# drveth.net
KiCad netlist of a schematic drawn in Altium Designer
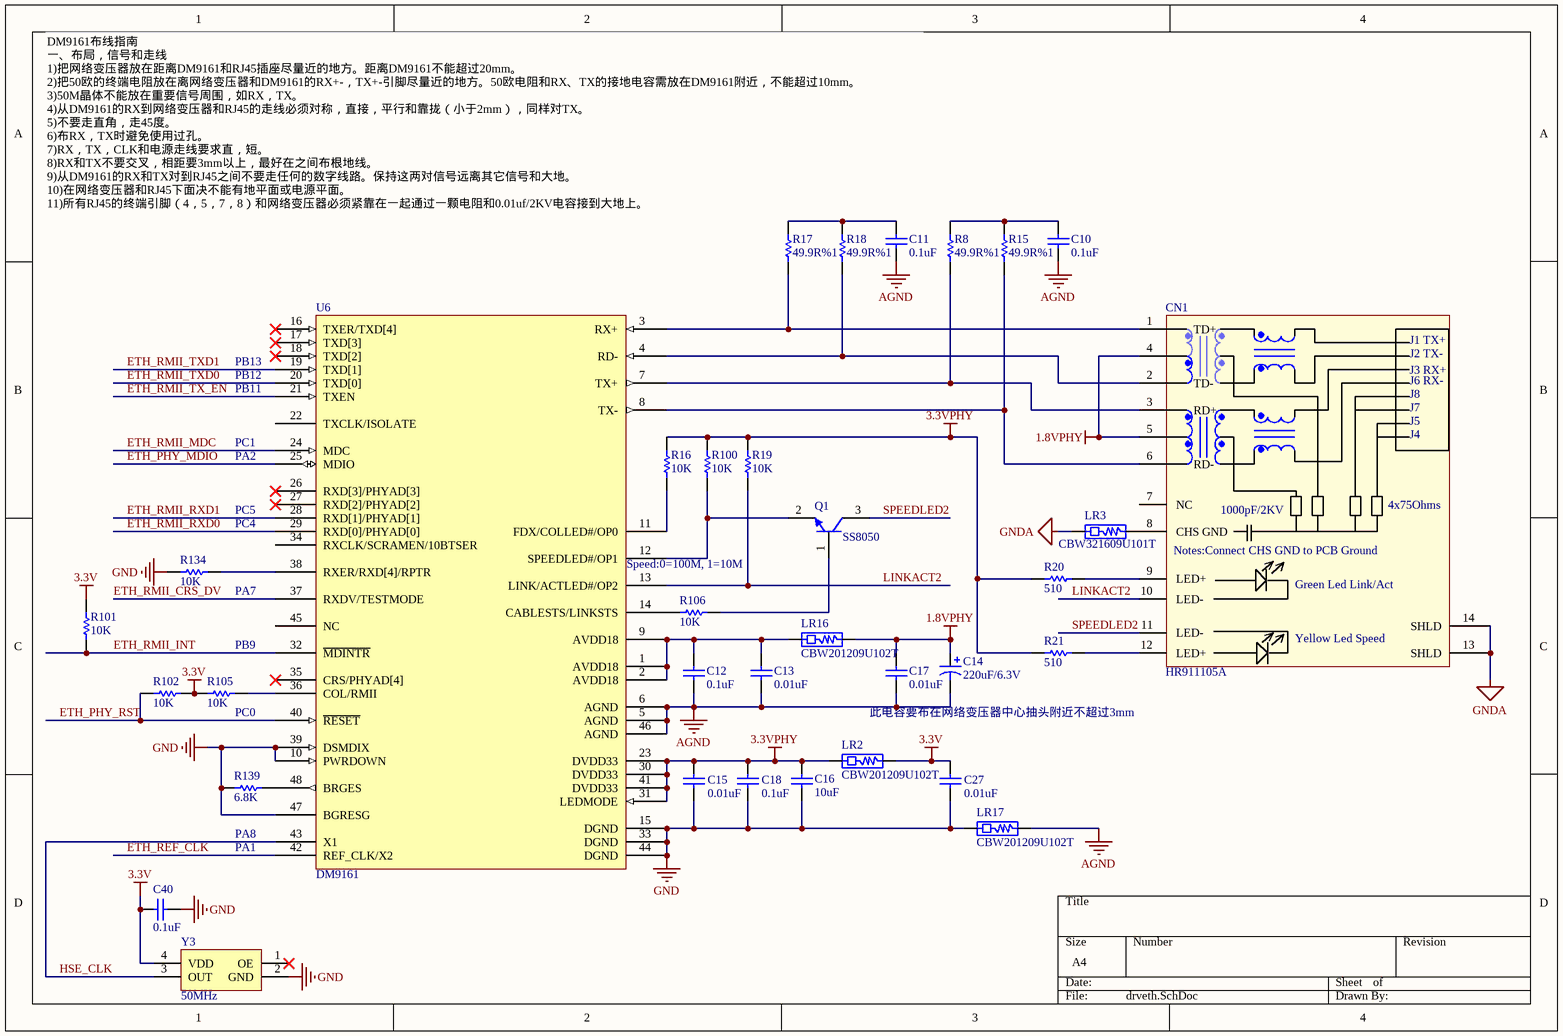
[diagram p0: drveth.SchDoc]

(export (version "E")
  (design (tool "Eeschema 10.0.6"))
  (components
    (comp (ref "C10")
      (value "0.1uF")
      (footprint "CAPC2012M")
      (description "Capacitor")
      (fields (field (name "PUBLISHER") "Altium Limited"))
      (libsource (lib "Miscellaneous Devices") (part "Cap"))
    )
    (comp (ref "C11")
      (value "0.1uF")
      (footprint "CAPC2012M")
      (description "Capacitor")
      (fields (field (name "PUBLISHER") "Altium Limited"))
      (libsource (lib "Miscellaneous Devices") (part "Cap"))
    )
    (comp (ref "C12")
      (value "0.1uF")
      (footprint "CAPC2012M")
      (description "Capacitor")
      (fields (field (name "PUBLISHER") "Altium Limited"))
      (libsource (lib "Miscellaneous Devices") (part "Cap"))
    )
    (comp (ref "C13")
      (value "0.01uF")
      (footprint "CAPC2012M")
      (description "Capacitor")
      (fields (field (name "PUBLISHER") "Altium Limited"))
      (libsource (lib "Miscellaneous Devices") (part "Cap"))
    )
    (comp (ref "C14")
      (value "220uF/6.3V")
      (footprint "CAPC3528MS")
      (description "Polarized Capacitor (Radial)")
      (fields (field (name "PUBLISHER") "Altium Limited"))
      (libsource (lib "Miscellaneous Devices") (part "Cap Pol1"))
    )
    (comp (ref "C15")
      (value "0.01uF")
      (footprint "CAPC2012M")
      (description "Capacitor")
      (fields (field (name "PUBLISHER") "Altium Limited"))
      (libsource (lib "Miscellaneous Devices") (part "Cap"))
    )
    (comp (ref "C16")
      (value "10uF")
      (footprint "CAPC2012M")
      (description "Capacitor")
      (fields (field (name "PUBLISHER") "Altium Limited"))
      (libsource (lib "Miscellaneous Devices") (part "Cap"))
    )
    (comp (ref "C17")
      (value "0.01uF")
      (footprint "CAPC2012M")
      (description "Capacitor")
      (fields (field (name "PUBLISHER") "Altium Limited"))
      (libsource (lib "Miscellaneous Devices") (part "Cap"))
    )
    (comp (ref "C18")
      (value "0.1uF")
      (footprint "CAPC2012M")
      (description "Capacitor")
      (fields (field (name "PUBLISHER") "Altium Limited"))
      (libsource (lib "Miscellaneous Devices") (part "Cap"))
    )
    (comp (ref "C27")
      (value "0.01uF")
      (footprint "CAPC2012M")
      (description "Capacitor")
      (fields (field (name "PUBLISHER") "Altium Limited"))
      (libsource (lib "Miscellaneous Devices") (part "Cap"))
    )
    (comp (ref "C40")
      (value "0.1uF")
      (footprint "CAPC2012M")
      (description "Capacitor")
      (fields (field (name "PUBLISHER") "Altium Limited"))
      (libsource (lib "Miscellaneous Devices") (part "Cap"))
    )
    (comp (ref "CN1")
      (value "HR911105A")
      (footprint "HR911105A(RJ-45)")
      (libsource (lib "UserSchDev") (part "HR911105A"))
    )
    (comp (ref "LR2")
      (value "CBW201209U102T")
      (footprint "INDC2012M")
      (description "EMI FILTERS,DC Resistance max.0.05~1.5 ohms,10 ~ 1000 ohms at 100MHz  Frequency")
      (libsource (lib "UserLib") (part "BLM10/11/21/31/41"))
    )
    (comp (ref "LR3")
      (value "CBW321609U101T")
      (footprint "INDC3216M")
      (description "EMI FILTERS,DC Resistance max.0.05~1.5 ohms,10 ~ 1000 ohms at 100MHz  Frequency")
      (libsource (lib "UserLib") (part "BLM10/11/21/31/41"))
    )
    (comp (ref "LR16")
      (value "CBW201209U102T")
      (footprint "INDC2012M")
      (description "EMI FILTERS,DC Resistance max.0.05~1.5 ohms,10 ~ 1000 ohms at 100MHz  Frequency")
      (libsource (lib "UserLib") (part "BLM10/11/21/31/41"))
    )
    (comp (ref "LR17")
      (value "CBW201209U102T")
      (footprint "INDC2012M")
      (description "EMI FILTERS,DC Resistance max.0.05~1.5 ohms,10 ~ 1000 ohms at 100MHz  Frequency")
      (libsource (lib "UserLib") (part "BLM10/11/21/31/41"))
    )
    (comp (ref "Q1")
      (value "SS8050")
      (footprint "SOT-23_N")
      (description "NPN BISS Transistor")
      (fields (field (name "PUBLISHER") "Altium Limited"))
      (libsource (lib "Philips Discrete BJT - Low Power") (part "PMMT491A"))
    )
    (comp (ref "R8")
      (value "49.9R%1")
      (footprint "RESC2012M")
      (description "Resistor")
      (fields (field (name "PUBLISHER") "Altium Limited"))
      (libsource (lib "Miscellaneous Devices") (part "Res1"))
    )
    (comp (ref "R15")
      (value "49.9R%1")
      (footprint "RESC2012M")
      (description "Resistor")
      (fields (field (name "PUBLISHER") "Altium Limited"))
      (libsource (lib "Miscellaneous Devices") (part "Res1"))
    )
    (comp (ref "R16")
      (value "10K")
      (footprint "RESC2012M")
      (description "Resistor")
      (fields (field (name "PUBLISHER") "Altium Limited"))
      (libsource (lib "Miscellaneous Devices") (part "Res1"))
    )
    (comp (ref "R17")
      (value "49.9R%1")
      (footprint "RESC2012M")
      (description "Resistor")
      (fields (field (name "PUBLISHER") "Altium Limited"))
      (libsource (lib "Miscellaneous Devices") (part "Res1"))
    )
    (comp (ref "R18")
      (value "49.9R%1")
      (footprint "RESC2012M")
      (description "Resistor")
      (fields (field (name "PUBLISHER") "Altium Limited"))
      (libsource (lib "Miscellaneous Devices") (part "Res1"))
    )
    (comp (ref "R19")
      (value "10K")
      (footprint "RESC2012M")
      (description "Resistor")
      (fields (field (name "PUBLISHER") "Altium Limited"))
      (libsource (lib "Miscellaneous Devices") (part "Res1"))
    )
    (comp (ref "R20")
      (value "510")
      (footprint "RESC2012M")
      (description "Resistor")
      (fields (field (name "PUBLISHER") "Altium Limited"))
      (libsource (lib "Miscellaneous Devices") (part "Res1"))
    )
    (comp (ref "R21")
      (value "510")
      (footprint "RESC2012M")
      (description "Resistor")
      (fields (field (name "PUBLISHER") "Altium Limited"))
      (libsource (lib "Miscellaneous Devices") (part "Res1"))
    )
    (comp (ref "R100")
      (value "10K")
      (footprint "RESC2012M")
      (description "Resistor")
      (fields (field (name "PUBLISHER") "Altium Limited"))
      (libsource (lib "Miscellaneous Devices") (part "Res1"))
    )
    (comp (ref "R101")
      (value "10K")
      (footprint "RESC2012M")
      (description "Resistor")
      (fields (field (name "PUBLISHER") "Altium Limited"))
      (libsource (lib "Miscellaneous Devices") (part "Res1"))
    )
    (comp (ref "R102")
      (value "10K")
      (footprint "RESC2012M")
      (description "Resistor")
      (fields (field (name "PUBLISHER") "Altium Limited"))
      (libsource (lib "Miscellaneous Devices") (part "Res1"))
    )
    (comp (ref "R105")
      (value "10K")
      (footprint "RESC2012M")
      (description "Resistor")
      (fields (field (name "PUBLISHER") "Altium Limited"))
      (libsource (lib "Miscellaneous Devices") (part "Res1"))
    )
    (comp (ref "R106")
      (value "10K")
      (footprint "RESC2012M")
      (description "Resistor")
      (fields (field (name "PUBLISHER") "Altium Limited"))
      (libsource (lib "Miscellaneous Devices") (part "Res1"))
    )
    (comp (ref "R134")
      (value "10K")
      (footprint "RESC2012M")
      (description "Resistor")
      (fields (field (name "PUBLISHER") "Altium Limited"))
      (libsource (lib "Miscellaneous Devices") (part "Res1"))
    )
    (comp (ref "R139")
      (value "6.8K")
      (footprint "RESC2012M")
      (description "Resistor")
      (fields (field (name "PUBLISHER") "Altium Limited"))
      (libsource (lib "Miscellaneous Devices") (part "Res1"))
    )
    (comp (ref "U6")
      (value "DM9161")
      (footprint "LQFP48_L")
      (description "网络芯片")
      (libsource (lib "UserSchDev") (part "DM9161"))
    )
    (comp (ref "Y3")
      (value "50MHz")
      (footprint "X-CP3225")
      (description "贴片有源晶振")
      (fields (field (name "Comment") "XATLS"))
      (libsource (lib "UserSchDev") (part "XATLS"))
    )
  )
  (nets
    (net (code "1") (name "/ETH_PHY_MDIO") (class "Default")
      (node (ref "U6") (pin "25") (pinfunction "MDIO_25") (pintype "bidirectional"))
    )
    (net (code "2") (name "/ETH_PHY_RST") (class "Default")
      (node (ref "R102") (pin "1") (pinfunction "1_1") (pintype "passive"))
      (node (ref "U6") (pin "40") (pinfunction "~{RESET}_40") (pintype "input"))
    )
    (net (code "3") (name "/ETH_REF_CLK") (class "Default")
      (node (ref "U6") (pin "42") (pinfunction "REF_CLK/X2_42") (pintype "passive"))
    )
    (net (code "4") (name "/ETH_RMII_CRS_DV") (class "Default")
      (node (ref "U6") (pin "37") (pinfunction "RXDV/TESTMODE_37") (pintype "passive"))
    )
    (net (code "5") (name "/ETH_RMII_INT") (class "Default")
      (node (ref "R101") (pin "2") (pinfunction "2_2") (pintype "passive"))
      (node (ref "U6") (pin "32") (pinfunction "~{MDINTR}_32") (pintype "passive"))
    )
    (net (code "6") (name "/ETH_RMII_MDC") (class "Default")
      (node (ref "U6") (pin "24") (pinfunction "MDC_24") (pintype "input"))
    )
    (net (code "7") (name "/ETH_RMII_RXD0") (class "Default")
      (node (ref "U6") (pin "29") (pinfunction "RXD[0]/PHYAD[0]_29") (pintype "passive"))
    )
    (net (code "8") (name "/ETH_RMII_RXD1") (class "Default")
      (node (ref "U6") (pin "28") (pinfunction "RXD[1]/PHYAD[1]_28") (pintype "passive"))
    )
    (net (code "9") (name "/ETH_RMII_TXD0") (class "Default")
      (node (ref "U6") (pin "20") (pinfunction "TXD[0]_20") (pintype "input"))
    )
    (net (code "10") (name "/ETH_RMII_TXD1") (class "Default")
      (node (ref "U6") (pin "19") (pinfunction "TXD[1]_19") (pintype "input"))
    )
    (net (code "11") (name "/ETH_RMII_TX_EN") (class "Default")
      (node (ref "U6") (pin "21") (pinfunction "TXEN_21") (pintype "input"))
    )
    (net (code "12") (name "/HSE_CLK") (class "Default")
      (node (ref "U6") (pin "43") (pinfunction "X1_43") (pintype "passive"))
      (node (ref "Y3") (pin "3") (pinfunction "OUT_3") (pintype "passive"))
    )
    (net (code "13") (name "/LINKACT2") (class "Default")
      (node (ref "CN1") (pin "10") (pinfunction "LED-_10") (pintype "passive"))
      (node (ref "R19") (pin "2") (pinfunction "2_2") (pintype "passive"))
      (node (ref "U6") (pin "13") (pinfunction "LINK/ACTLED#/OP2_13") (pintype "passive"))
    )
    (net (code "14") (name "/SPEEDLED2") (class "Default")
      (node (ref "CN1") (pin "11") (pinfunction "LED-_11") (pintype "passive"))
      (node (ref "Q1") (pin "3") (pinfunction "C_3") (pintype "passive"))
    )
    (net (code "15") (name "1.8VPHY") (class "Default")
      (node (ref "C14") (pin "1") (pinfunction "1_1") (pintype "passive"))
      (node (ref "C17") (pin "1") (pinfunction "1_1") (pintype "passive"))
      (node (ref "CN1") (pin "4") (pintype "passive"))
      (node (ref "CN1") (pin "5") (pintype "passive"))
      (node (ref "LR16") (pin "1") (pinfunction "1_1") (pintype "passive"))
    )
    (net (code "16") (name "3.3V") (class "Default")
      (node (ref "C27") (pin "1") (pinfunction "1_1") (pintype "passive"))
      (node (ref "C40") (pin "1") (pinfunction "1_1") (pintype "passive"))
      (node (ref "LR2") (pin "1") (pinfunction "1_1") (pintype "passive"))
      (node (ref "R101") (pin "1") (pinfunction "1_1") (pintype "passive"))
      (node (ref "R102") (pin "2") (pinfunction "2_2") (pintype "passive"))
      (node (ref "R105") (pin "1") (pinfunction "1_1") (pintype "passive"))
      (node (ref "Y3") (pin "4") (pinfunction "VDD_4") (pintype "passive"))
    )
    (net (code "17") (name "3.3VPHY") (class "Default")
      (node (ref "C15") (pin "1") (pinfunction "1_1") (pintype "passive"))
      (node (ref "C16") (pin "1") (pinfunction "1_1") (pintype "passive"))
      (node (ref "C18") (pin "1") (pinfunction "1_1") (pintype "passive"))
      (node (ref "LR2") (pin "2") (pinfunction "2_2") (pintype "passive"))
      (node (ref "R100") (pin "1") (pinfunction "1_1") (pintype "passive"))
      (node (ref "R16") (pin "1") (pinfunction "1_1") (pintype "passive"))
      (node (ref "R19") (pin "1") (pinfunction "1_1") (pintype "passive"))
      (node (ref "R20") (pin "1") (pinfunction "1_1") (pintype "passive"))
      (node (ref "R21") (pin "1") (pinfunction "1_1") (pintype "passive"))
      (node (ref "U6") (pin "23") (pinfunction "DVDD33_23") (pintype "power_in"))
      (node (ref "U6") (pin "30") (pinfunction "DVDD33_30") (pintype "power_in"))
      (node (ref "U6") (pin "31") (pinfunction "LEDMODE_31") (pintype "input"))
      (node (ref "U6") (pin "41") (pinfunction "DVDD33_41") (pintype "power_in"))
    )
    (net (code "18") (name "AGND") (class "Default")
      (node (ref "C10") (pin "2") (pinfunction "2_2") (pintype "passive"))
      (node (ref "C11") (pin "2") (pinfunction "2_2") (pintype "passive"))
      (node (ref "C12") (pin "2") (pinfunction "2_2") (pintype "passive"))
      (node (ref "C13") (pin "2") (pinfunction "2_2") (pintype "passive"))
      (node (ref "C14") (pin "2") (pinfunction "2_2") (pintype "passive"))
      (node (ref "C17") (pin "2") (pinfunction "2_2") (pintype "passive"))
      (node (ref "LR17") (pin "1") (pinfunction "1_1") (pintype "passive"))
      (node (ref "U6") (pin "46") (pinfunction "AGND_46") (pintype "power_in"))
      (node (ref "U6") (pin "5") (pinfunction "AGND_5") (pintype "power_in"))
      (node (ref "U6") (pin "6") (pinfunction "AGND_6") (pintype "power_in"))
    )
    (net (code "19") (name "GND") (class "Default")
      (node (ref "C15") (pin "2") (pinfunction "2_2") (pintype "passive"))
      (node (ref "C16") (pin "2") (pinfunction "2_2") (pintype "passive"))
      (node (ref "C18") (pin "2") (pinfunction "2_2") (pintype "passive"))
      (node (ref "C27") (pin "2") (pinfunction "2_2") (pintype "passive"))
      (node (ref "C40") (pin "2") (pinfunction "2_2") (pintype "passive"))
      (node (ref "LR17") (pin "2") (pinfunction "2_2") (pintype "passive"))
      (node (ref "R134") (pin "1") (pinfunction "1_1") (pintype "passive"))
      (node (ref "R139") (pin "1") (pinfunction "1_1") (pintype "passive"))
      (node (ref "U6") (pin "10") (pinfunction "PWRDOWN_10") (pintype "input"))
      (node (ref "U6") (pin "15") (pinfunction "DGND_15") (pintype "power_in"))
      (node (ref "U6") (pin "33") (pinfunction "DGND_33") (pintype "passive"))
      (node (ref "U6") (pin "39") (pinfunction "DSMDIX_39") (pintype "input"))
      (node (ref "U6") (pin "44") (pinfunction "DGND_44") (pintype "passive"))
      (node (ref "U6") (pin "47") (pinfunction "BGRESG_47") (pintype "power_in"))
      (node (ref "Y3") (pin "2") (pinfunction "GND_2") (pintype "passive"))
    )
    (net (code "20") (name "GNDA") (class "Default")
      (node (ref "CN1") (pin "13") (pinfunction "SHLD_13") (pintype "passive"))
      (node (ref "CN1") (pin "14") (pinfunction "SHLD_14") (pintype "passive"))
      (node (ref "LR3") (pin "2") (pinfunction "2_2") (pintype "passive"))
    )
    (net (code "21") (name "Net-(C10-Pad1)") (class "Default")
      (node (ref "C10") (pin "1") (pinfunction "1_1") (pintype "passive"))
      (node (ref "R15") (pin "1") (pinfunction "1_1") (pintype "passive"))
      (node (ref "R8") (pin "1") (pinfunction "1_1") (pintype "passive"))
    )
    (net (code "22") (name "Net-(C11-Pad1)") (class "Default")
      (node (ref "C11") (pin "1") (pinfunction "1_1") (pintype "passive"))
      (node (ref "R17") (pin "1") (pinfunction "1_1") (pintype "passive"))
      (node (ref "R18") (pin "1") (pinfunction "1_1") (pintype "passive"))
    )
    (net (code "23") (name "Net-(C12-Pad1)") (class "Default")
      (node (ref "C12") (pin "1") (pinfunction "1_1") (pintype "passive"))
      (node (ref "C13") (pin "1") (pinfunction "1_1") (pintype "passive"))
      (node (ref "LR16") (pin "2") (pinfunction "2_2") (pintype "passive"))
      (node (ref "U6") (pin "1") (pinfunction "AVDD18_1") (pintype "power_in"))
      (node (ref "U6") (pin "2") (pinfunction "AVDD18_2") (pintype "power_in"))
      (node (ref "U6") (pin "9") (pinfunction "AVDD18_9") (pintype "power_in"))
    )
    (net (code "24") (name "Net-(CN1-CHS_GND)") (class "Default")
      (node (ref "CN1") (pin "8") (pinfunction "CHS_GND_8") (pintype "passive"))
      (node (ref "LR3") (pin "1") (pinfunction "1_1") (pintype "passive"))
    )
    (net (code "25") (name "Net-(CN1-LED+-Pad9)") (class "Default")
      (node (ref "CN1") (pin "9") (pinfunction "LED+_9") (pintype "passive"))
      (node (ref "R20") (pin "2") (pinfunction "2_2") (pintype "passive"))
    )
    (net (code "26") (name "Net-(CN1-LED+-Pad12)") (class "Default")
      (node (ref "CN1") (pin "12") (pinfunction "LED+_12") (pintype "passive"))
      (node (ref "R21") (pin "2") (pinfunction "2_2") (pintype "passive"))
    )
    (net (code "27") (name "Net-(CN1-RD+)") (class "Default")
      (node (ref "CN1") (pin "3") (pinfunction "RD+_3") (pintype "passive"))
      (node (ref "R8") (pin "2") (pinfunction "2_2") (pintype "passive"))
      (node (ref "U6") (pin "7") (pinfunction "TX+_7") (pintype "output"))
    )
    (net (code "28") (name "Net-(CN1-RD-)") (class "Default")
      (node (ref "CN1") (pin "6") (pinfunction "RD-_6") (pintype "passive"))
      (node (ref "R15") (pin "2") (pinfunction "2_2") (pintype "passive"))
      (node (ref "U6") (pin "8") (pinfunction "TX-_8") (pintype "output"))
    )
    (net (code "29") (name "Net-(CN1-TD+)") (class "Default")
      (node (ref "CN1") (pin "1") (pinfunction "TD+_1") (pintype "passive"))
      (node (ref "R17") (pin "2") (pinfunction "2_2") (pintype "passive"))
      (node (ref "U6") (pin "3") (pinfunction "RX+_3") (pintype "input"))
    )
    (net (code "30") (name "Net-(CN1-TD-)") (class "Default")
      (node (ref "CN1") (pin "2") (pinfunction "TD-_2") (pintype "passive"))
      (node (ref "R18") (pin "2") (pinfunction "2_2") (pintype "passive"))
      (node (ref "U6") (pin "4") (pinfunction "RD-_4") (pintype "input"))
    )
    (net (code "31") (name "Net-(Q1-B)") (class "Default")
      (node (ref "Q1") (pin "1") (pinfunction "B_1") (pintype "passive"))
      (node (ref "R106") (pin "2") (pinfunction "2_2") (pintype "passive"))
    )
    (net (code "32") (name "Net-(Q1-E)") (class "Default")
      (node (ref "Q1") (pin "2") (pinfunction "E_2") (pintype "passive"))
      (node (ref "R100") (pin "2") (pinfunction "2_2") (pintype "passive"))
      (node (ref "U6") (pin "12") (pinfunction "SPEEDLED#/OP1_12") (pintype "passive"))
    )
    (net (code "33") (name "Net-(U6-BRGES)") (class "Default")
      (node (ref "R139") (pin "2") (pinfunction "2_2") (pintype "passive"))
      (node (ref "U6") (pin "48") (pinfunction "BRGES_48") (pintype "output"))
    )
    (net (code "34") (name "Net-(U6-CABLESTS{slash}LINKSTS)") (class "Default")
      (node (ref "R106") (pin "1") (pinfunction "1_1") (pintype "passive"))
      (node (ref "U6") (pin "14") (pinfunction "CABLESTS/LINKSTS_14") (pintype "passive"))
    )
    (net (code "35") (name "Net-(U6-COL{slash}RMII)") (class "Default")
      (node (ref "R105") (pin "2") (pinfunction "2_2") (pintype "passive"))
      (node (ref "U6") (pin "36") (pinfunction "COL/RMII_36") (pintype "passive"))
    )
    (net (code "36") (name "Net-(U6-FDX{slash}COLLED#{slash}OP0)") (class "Default")
      (node (ref "R16") (pin "2") (pinfunction "2_2") (pintype "passive"))
      (node (ref "U6") (pin "11") (pinfunction "FDX/COLLED#/OP0_11") (pintype "passive"))
    )
    (net (code "37") (name "Net-(U6-RXER{slash}RXD[4]{slash}RPTR)") (class "Default")
      (node (ref "R134") (pin "2") (pinfunction "2_2") (pintype "passive"))
      (node (ref "U6") (pin "38") (pinfunction "RXER/RXD[4]/RPTR_38") (pintype "passive"))
    )
    (net (code "38") (name "unconnected-(CN1-NC-Pad7)") (class "Default")
      (node (ref "CN1") (pin "7") (pinfunction "NC_7") (pintype "passive"))
    )
    (net (code "39") (name "unconnected-(U6-CRS{slash}PHYAD[4]-Pad35)") (class "Default")
      (node (ref "U6") (pin "35") (pinfunction "CRS/PHYAD[4]_35") (pintype "passive+no_connect"))
    )
    (net (code "40") (name "unconnected-(U6-NC-Pad45)") (class "Default")
      (node (ref "U6") (pin "45") (pinfunction "NC_45") (pintype "passive"))
    )
    (net (code "41") (name "unconnected-(U6-RXCLK{slash}SCRAMEN{slash}10BTSER-Pad34)") (class "Default")
      (node (ref "U6") (pin "34") (pinfunction "RXCLK/SCRAMEN/10BTSER_34") (pintype "passive"))
    )
    (net (code "42") (name "unconnected-(U6-RXD[2]{slash}PHYAD[2]-Pad27)") (class "Default")
      (node (ref "U6") (pin "27") (pinfunction "RXD[2]/PHYAD[2]_27") (pintype "passive+no_connect"))
    )
    (net (code "43") (name "unconnected-(U6-RXD[3]{slash}PHYAD[3]-Pad26)") (class "Default")
      (node (ref "U6") (pin "26") (pinfunction "RXD[3]/PHYAD[3]_26") (pintype "passive+no_connect"))
    )
    (net (code "44") (name "unconnected-(U6-TXCLK{slash}ISOLATE-Pad22)") (class "Default")
      (node (ref "U6") (pin "22") (pinfunction "TXCLK/ISOLATE_22") (pintype "passive"))
    )
    (net (code "45") (name "unconnected-(U6-TXD[2]-Pad18)") (class "Default")
      (node (ref "U6") (pin "18") (pinfunction "TXD[2]_18") (pintype "input+no_connect"))
    )
    (net (code "46") (name "unconnected-(U6-TXD[3]-Pad17)") (class "Default")
      (node (ref "U6") (pin "17") (pinfunction "TXD[3]_17") (pintype "input+no_connect"))
    )
    (net (code "47") (name "unconnected-(U6-TXER{slash}TXD[4]-Pad16)") (class "Default")
      (node (ref "U6") (pin "16") (pinfunction "TXER/TXD[4]_16") (pintype "input+no_connect"))
    )
    (net (code "48") (name "unconnected-(Y3-OE-Pad1)") (class "Default")
      (node (ref "Y3") (pin "1") (pinfunction "OE_1") (pintype "passive+no_connect"))
    )
  )
)
